# Globe_V3.net
KiCad netlist of a schematic drawn in EAGLE
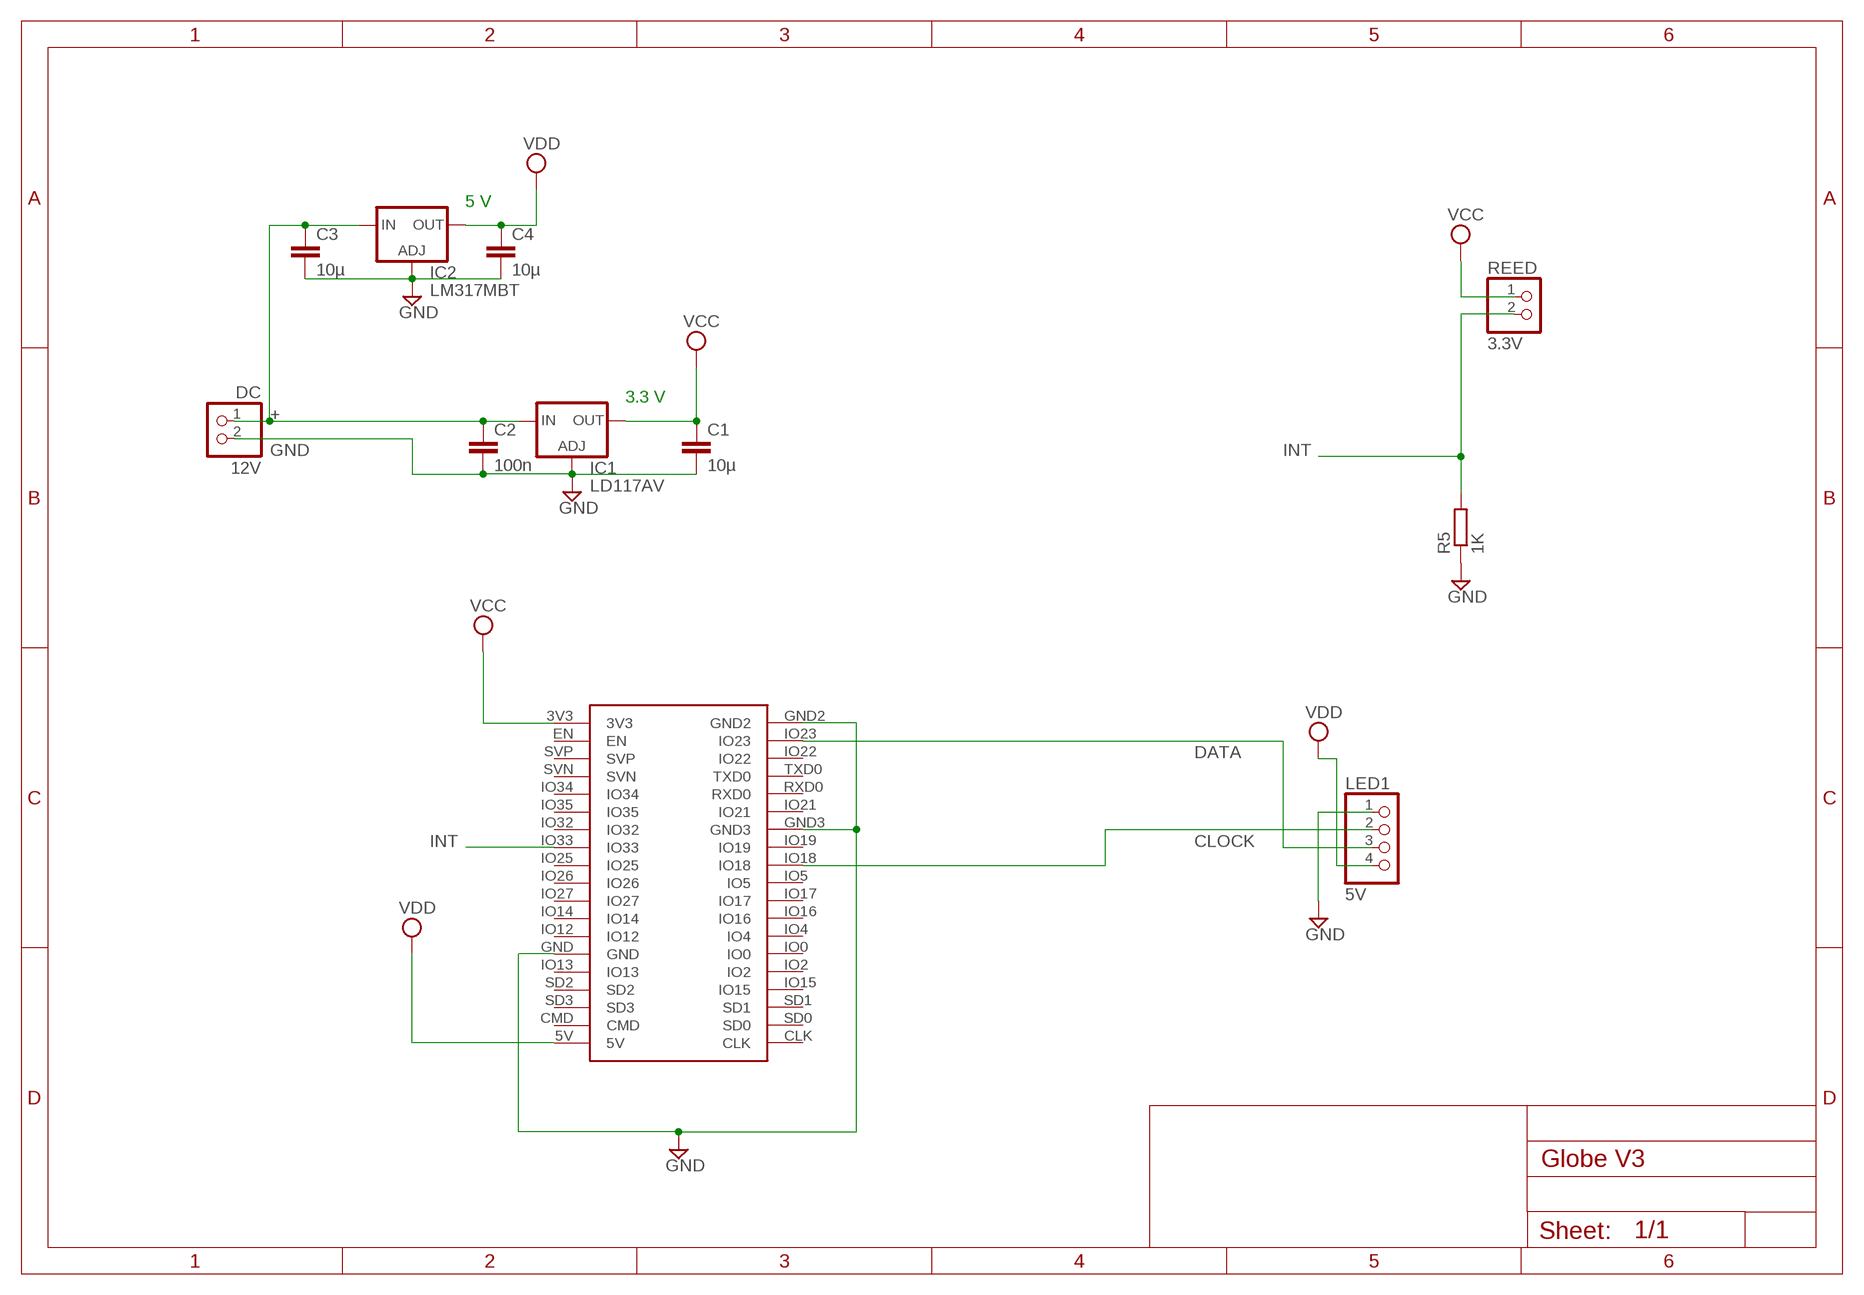
[diagram p0: schematic, sheet 1]

(export (version "E")
  (design (tool "Eeschema 10.0.6"))
  (components
    (comp (ref "C1")
      (value "10µ")
      (footprint "eagle-import:C025-024X044")
      (libsource (lib "eagle-import") (part "C-EU025-024X044"))
    )
    (comp (ref "C2")
      (value "100n")
      (footprint "eagle-import:C050-024X044")
      (libsource (lib "eagle-import") (part "C-EU050-024X044"))
    )
    (comp (ref "C3")
      (value "10µ")
      (footprint "eagle-import:C025-024X044")
      (libsource (lib "eagle-import") (part "C-EU025-024X044"))
    )
    (comp (ref "C4")
      (value "10µ")
      (footprint "eagle-import:C025-024X044")
      (libsource (lib "eagle-import") (part "C-EU025-024X044"))
    )
    (comp (ref "DC")
      (value "12V")
      (footprint "eagle-import:1X02")
      (libsource (lib "eagle-import") (part "PINHD-1X2"))
    )
    (comp (ref "IC1")
      (value "LD117AV")
      (footprint "eagle-import:TO220L1")
      (libsource (lib "eagle-import") (part "LD117A?V"))
    )
    (comp (ref "IC2")
      (value "LM317MBT")
      (footprint "eagle-import:TO220L1")
      (libsource (lib "eagle-import") (part "LM317?MBT"))
    )
    (comp (ref "LED1")
      (value "5V")
      (footprint "eagle-import:1X04")
      (libsource (lib "eagle-import") (part "PINHD-1X4"))
    )
    (comp (ref "R5")
      (value "1K")
      (footprint "eagle-import:0207_10")
      (libsource (lib "eagle-import") (part "R-EU_0207/10"))
    )
    (comp (ref "REED")
      (value "3.3V")
      (footprint "eagle-import:1X02")
      (libsource (lib "eagle-import") (part "PINHD-1X2"))
    )
    (comp (ref "U$1")
      (value "ESP32_DEVKITC")
      (footprint "eagle-import:ESP32_DEVKITC")
      (libsource (lib "eagle-import") (part "ESP32_DEVKITC"))
    )
  )
  (nets
    (net (code "1") (name "/+") (class "Default")
      (node (ref "C2") (pin "1") (pinfunction "1_1") (pintype "passive"))
      (node (ref "C3") (pin "1") (pinfunction "1_1") (pintype "passive"))
      (node (ref "DC") (pin "1") (pinfunction "1_1") (pintype "passive"))
      (node (ref "IC1") (pin "3") (pinfunction "IN_3") (pintype "input"))
      (node (ref "IC2") (pin "3") (pinfunction "IN_3") (pintype "input"))
    )
    (net (code "2") (name "/CLOCK") (class "Default")
      (node (ref "LED1") (pin "2") (pinfunction "2_2") (pintype "passive"))
      (node (ref "U$1") (pin "IO18") (pinfunction "IO18_IO18") (pintype "bidirectional"))
    )
    (net (code "3") (name "/DATA") (class "Default")
      (node (ref "LED1") (pin "3") (pinfunction "3_3") (pintype "passive"))
      (node (ref "U$1") (pin "IO23") (pinfunction "IO23_IO23") (pintype "bidirectional"))
    )
    (net (code "4") (name "/INT") (class "Default")
      (node (ref "R5") (pin "2") (pinfunction "2_2") (pintype "passive"))
      (node (ref "REED") (pin "2") (pinfunction "2_2") (pintype "passive"))
      (node (ref "U$1") (pin "IO33") (pinfunction "IO33_IO33") (pintype "bidirectional"))
    )
    (net (code "5") (name "GND") (class "Default")
      (node (ref "C1") (pin "2") (pinfunction "2_2") (pintype "passive"))
      (node (ref "C2") (pin "2") (pinfunction "2_2") (pintype "passive"))
      (node (ref "C3") (pin "2") (pinfunction "2_2") (pintype "passive"))
      (node (ref "C4") (pin "2") (pinfunction "2_2") (pintype "passive"))
      (node (ref "DC") (pin "2") (pinfunction "2_2") (pintype "passive"))
      (node (ref "IC1") (pin "1") (pinfunction "ADJ_1") (pintype "input"))
      (node (ref "IC2") (pin "1") (pinfunction "ADJ_1") (pintype "input"))
      (node (ref "LED1") (pin "1") (pinfunction "1_1") (pintype "passive"))
      (node (ref "R5") (pin "1") (pinfunction "1_1") (pintype "passive"))
      (node (ref "U$1") (pin "GND") (pinfunction "GND_GND") (pintype "bidirectional"))
      (node (ref "U$1") (pin "GND2") (pinfunction "GND2_GND2") (pintype "bidirectional"))
      (node (ref "U$1") (pin "GND3") (pinfunction "GND3_GND3") (pintype "bidirectional"))
    )
    (net (code "6") (name "VCC") (class "Default")
      (node (ref "C1") (pin "1") (pinfunction "1_1") (pintype "passive"))
      (node (ref "IC1") (pin "2") (pinfunction "OUT_2") (pintype "passive"))
      (node (ref "REED") (pin "1") (pinfunction "1_1") (pintype "passive"))
      (node (ref "U$1") (pin "3V3") (pinfunction "3V3_3V3") (pintype "bidirectional"))
    )
    (net (code "7") (name "VDD") (class "Default")
      (node (ref "C4") (pin "1") (pinfunction "1_1") (pintype "passive"))
      (node (ref "IC2") (pin "2") (pinfunction "OUT_2") (pintype "passive"))
      (node (ref "LED1") (pin "4") (pinfunction "4_4") (pintype "passive"))
      (node (ref "U$1") (pin "5V") (pinfunction "5V_5V") (pintype "bidirectional"))
    )
    (net (code "8") (name "unconnected-(U$1-PadCLK)") (class "Default")
      (node (ref "U$1") (pin "CLK") (pinfunction "CLK_CLK") (pintype "bidirectional"))
    )
    (net (code "9") (name "unconnected-(U$1-PadCMD)") (class "Default")
      (node (ref "U$1") (pin "CMD") (pinfunction "CMD_CMD") (pintype "bidirectional"))
    )
    (net (code "10") (name "unconnected-(U$1-PadEN)") (class "Default")
      (node (ref "U$1") (pin "EN") (pinfunction "EN_EN") (pintype "bidirectional"))
    )
    (net (code "11") (name "unconnected-(U$1-PadIO0)") (class "Default")
      (node (ref "U$1") (pin "IO0") (pinfunction "IO0_IO0") (pintype "bidirectional"))
    )
    (net (code "12") (name "unconnected-(U$1-PadIO2)") (class "Default")
      (node (ref "U$1") (pin "IO2") (pinfunction "IO2_IO2") (pintype "bidirectional"))
    )
    (net (code "13") (name "unconnected-(U$1-PadIO4)") (class "Default")
      (node (ref "U$1") (pin "IO4") (pinfunction "IO4_IO4") (pintype "bidirectional"))
    )
    (net (code "14") (name "unconnected-(U$1-PadIO5)") (class "Default")
      (node (ref "U$1") (pin "IO5") (pinfunction "IO5_IO5") (pintype "bidirectional"))
    )
    (net (code "15") (name "unconnected-(U$1-PadIO12)") (class "Default")
      (node (ref "U$1") (pin "IO12") (pinfunction "IO12_IO12") (pintype "bidirectional"))
    )
    (net (code "16") (name "unconnected-(U$1-PadIO13)") (class "Default")
      (node (ref "U$1") (pin "IO13") (pinfunction "IO13_IO13") (pintype "bidirectional"))
    )
    (net (code "17") (name "unconnected-(U$1-PadIO14)") (class "Default")
      (node (ref "U$1") (pin "IO14") (pinfunction "IO14_IO14") (pintype "bidirectional"))
    )
    (net (code "18") (name "unconnected-(U$1-PadIO15)") (class "Default")
      (node (ref "U$1") (pin "IO15") (pinfunction "IO15_IO15") (pintype "bidirectional"))
    )
    (net (code "19") (name "unconnected-(U$1-PadIO16)") (class "Default")
      (node (ref "U$1") (pin "IO16") (pinfunction "IO16_IO16") (pintype "bidirectional"))
    )
    (net (code "20") (name "unconnected-(U$1-PadIO17)") (class "Default")
      (node (ref "U$1") (pin "IO17") (pinfunction "IO17_IO17") (pintype "bidirectional"))
    )
    (net (code "21") (name "unconnected-(U$1-PadIO19)") (class "Default")
      (node (ref "U$1") (pin "IO19") (pinfunction "IO19_IO19") (pintype "bidirectional"))
    )
    (net (code "22") (name "unconnected-(U$1-PadIO21)") (class "Default")
      (node (ref "U$1") (pin "IO21") (pinfunction "IO21_IO21") (pintype "bidirectional"))
    )
    (net (code "23") (name "unconnected-(U$1-PadIO22)") (class "Default")
      (node (ref "U$1") (pin "IO22") (pinfunction "IO22_IO22") (pintype "bidirectional"))
    )
    (net (code "24") (name "unconnected-(U$1-PadIO25)") (class "Default")
      (node (ref "U$1") (pin "IO25") (pinfunction "IO25_IO25") (pintype "bidirectional"))
    )
    (net (code "25") (name "unconnected-(U$1-PadIO26)") (class "Default")
      (node (ref "U$1") (pin "IO26") (pinfunction "IO26_IO26") (pintype "bidirectional"))
    )
    (net (code "26") (name "unconnected-(U$1-PadIO27)") (class "Default")
      (node (ref "U$1") (pin "IO27") (pinfunction "IO27_IO27") (pintype "bidirectional"))
    )
    (net (code "27") (name "unconnected-(U$1-PadIO32)") (class "Default")
      (node (ref "U$1") (pin "IO32") (pinfunction "IO32_IO32") (pintype "bidirectional"))
    )
    (net (code "28") (name "unconnected-(U$1-PadIO34)") (class "Default")
      (node (ref "U$1") (pin "IO34") (pinfunction "IO34_IO34") (pintype "bidirectional"))
    )
    (net (code "29") (name "unconnected-(U$1-PadIO35)") (class "Default")
      (node (ref "U$1") (pin "IO35") (pinfunction "IO35_IO35") (pintype "bidirectional"))
    )
    (net (code "30") (name "unconnected-(U$1-PadRXD0)") (class "Default")
      (node (ref "U$1") (pin "RXD0") (pinfunction "RXD0_RXD0") (pintype "bidirectional"))
    )
    (net (code "31") (name "unconnected-(U$1-PadSD0)") (class "Default")
      (node (ref "U$1") (pin "SD0") (pinfunction "SD0_SD0") (pintype "bidirectional"))
    )
    (net (code "32") (name "unconnected-(U$1-PadSD1)") (class "Default")
      (node (ref "U$1") (pin "SD1") (pinfunction "SD1_SD1") (pintype "bidirectional"))
    )
    (net (code "33") (name "unconnected-(U$1-PadSD2)") (class "Default")
      (node (ref "U$1") (pin "SD2") (pinfunction "SD2_SD2") (pintype "bidirectional"))
    )
    (net (code "34") (name "unconnected-(U$1-PadSD3)") (class "Default")
      (node (ref "U$1") (pin "SD3") (pinfunction "SD3_SD3") (pintype "bidirectional"))
    )
    (net (code "35") (name "unconnected-(U$1-PadSVN)") (class "Default")
      (node (ref "U$1") (pin "SVN") (pinfunction "SVN_SVN") (pintype "bidirectional"))
    )
    (net (code "36") (name "unconnected-(U$1-PadSVP)") (class "Default")
      (node (ref "U$1") (pin "SVP") (pinfunction "SVP_SVP") (pintype "bidirectional"))
    )
    (net (code "37") (name "unconnected-(U$1-PadTXD0)") (class "Default")
      (node (ref "U$1") (pin "TXD0") (pinfunction "TXD0_TXD0") (pintype "bidirectional"))
    )
  )
)
